# Sheet2.net
KiCad netlist of a schematic drawn in Altium Designer
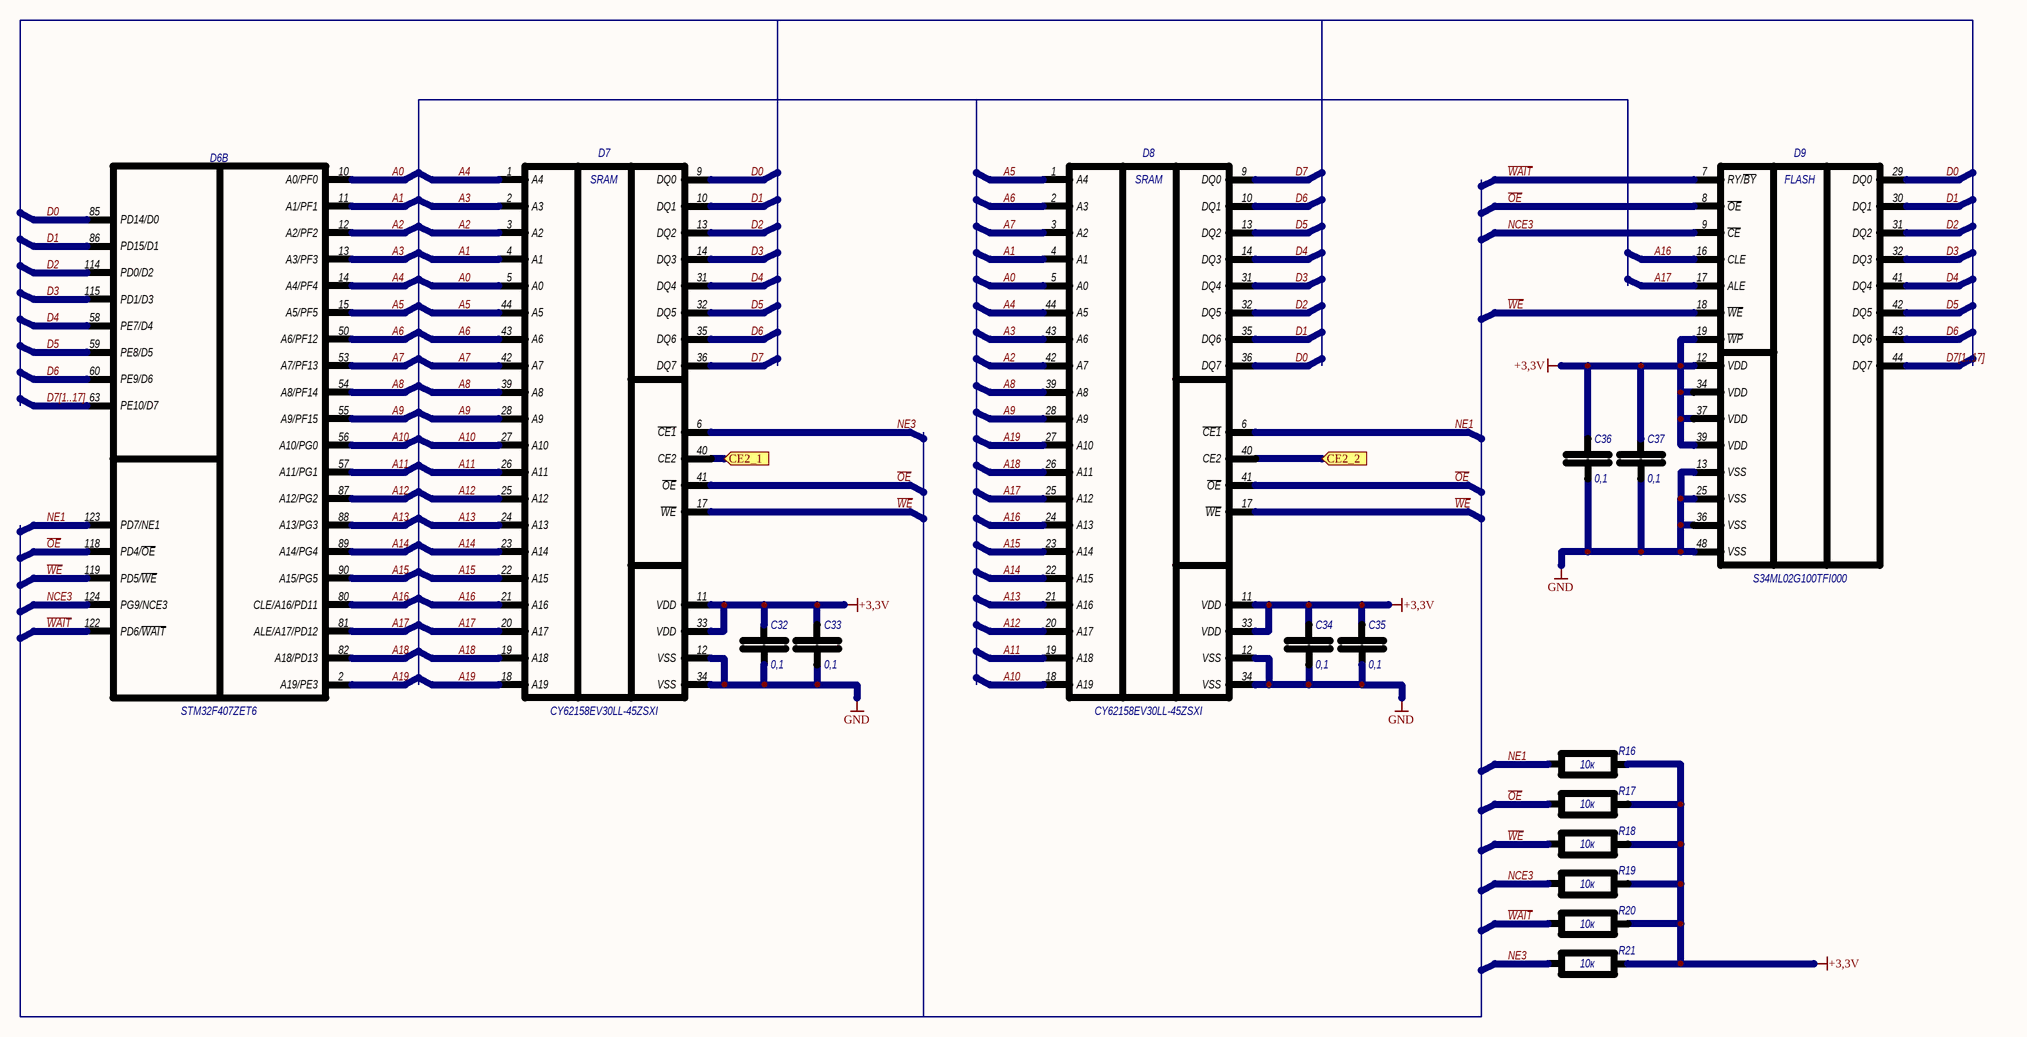
[diagram p0: Sheet2.SCHDOC]

(export (version "E")
  (design (tool "Eeschema 10.0.6"))
  (components
    (comp (ref "C32")
      (value "0,1")
      (footprint "0805")
      (description "КОНДЕНСАТОР")
      (fields (field (name "Comment") "К0805"))
      (libsource (lib "*") (part "К0805"))
    )
    (comp (ref "C33")
      (value "0,1")
      (footprint "0805")
      (description "КОНДЕНСАТОР")
      (fields (field (name "Comment") "К0805"))
      (libsource (lib "*") (part "К0805"))
    )
    (comp (ref "C34")
      (value "0,1")
      (footprint "0805")
      (description "КОНДЕНСАТОР")
      (fields (field (name "Comment") "К0805"))
      (libsource (lib "*") (part "К0805"))
    )
    (comp (ref "C35")
      (value "0,1")
      (footprint "0805")
      (description "КОНДЕНСАТОР")
      (fields (field (name "Comment") "К0805"))
      (libsource (lib "*") (part "К0805"))
    )
    (comp (ref "C36")
      (value "0,1")
      (footprint "0805")
      (description "КОНДЕНСАТОР")
      (fields (field (name "Comment") "К0805"))
      (libsource (lib "*") (part "К0805"))
    )
    (comp (ref "C37")
      (value "0,1")
      (footprint "0805")
      (description "КОНДЕНСАТОР")
      (fields (field (name "Comment") "К0805"))
      (libsource (lib "*") (part "К0805"))
    )
    (comp (ref "D6")
      (value "STM32F407ZET6")
      (footprint "LQFP-144")
      (libsource (lib "*") (part "STM32F407ZET6"))
    )
    (comp (ref "D7")
      (value "CY62158EV30LL-45ZSXI")
      (footprint "TSOP-44")
      (libsource (lib "*") (part "CY62158EV30LL-45ZSXI"))
    )
    (comp (ref "D8")
      (value "CY62158EV30LL-45ZSXI")
      (footprint "TSOP-44")
      (libsource (lib "*") (part "CY62158EV30LL-45ZSXI"))
    )
    (comp (ref "D9")
      (value "S34ML02G100TFI000")
      (footprint "TSSOP2-48")
      (libsource (lib "*") (part "S34ML02G100TFI000"))
    )
    (comp (ref "R16")
      (value "Р0805")
      (footprint "0805")
      (description "РЕЗИСТОР")
      (fields (field (name "ALTIUM_UNNAMED_1") "10к"))
      (libsource (lib "*") (part "Р0805"))
    )
    (comp (ref "R17")
      (value "Р0805")
      (footprint "0805")
      (description "РЕЗИСТОР")
      (fields (field (name "ALTIUM_UNNAMED_1") "10к"))
      (libsource (lib "*") (part "Р0805"))
    )
    (comp (ref "R18")
      (value "Р0805")
      (footprint "0805")
      (description "РЕЗИСТОР")
      (fields (field (name "ALTIUM_UNNAMED_1") "10к"))
      (libsource (lib "*") (part "Р0805"))
    )
    (comp (ref "R19")
      (value "Р0805")
      (footprint "0805")
      (description "РЕЗИСТОР")
      (fields (field (name "ALTIUM_UNNAMED_1") "10к"))
      (libsource (lib "*") (part "Р0805"))
    )
    (comp (ref "R20")
      (value "Р0805")
      (footprint "0805")
      (description "РЕЗИСТОР")
      (fields (field (name "ALTIUM_UNNAMED_1") "10к"))
      (libsource (lib "*") (part "Р0805"))
    )
    (comp (ref "R21")
      (value "Р0805")
      (footprint "0805")
      (description "РЕЗИСТОР")
      (fields (field (name "ALTIUM_UNNAMED_1") "10к"))
      (libsource (lib "*") (part "Р0805"))
    )
  )
  (nets
    (net (code "18") (name "+3,3V") (class "Default")
      (node (ref "C32") (pin "2") (pinfunction "2_2") (pintype "passive"))
      (node (ref "C33") (pin "2") (pinfunction "2_2") (pintype "passive"))
      (node (ref "C34") (pin "2") (pinfunction "2_2") (pintype "passive"))
      (node (ref "C35") (pin "2") (pinfunction "2_2") (pintype "passive"))
      (node (ref "C36") (pin "2") (pinfunction "2_2") (pintype "passive"))
      (node (ref "C37") (pin "2") (pinfunction "2_2") (pintype "passive"))
      (node (ref "D7") (pin "11") (pinfunction "VDD_11") (pintype "passive"))
      (node (ref "D7") (pin "33") (pinfunction "VDD_33") (pintype "passive"))
      (node (ref "D8") (pin "11") (pinfunction "VDD_11") (pintype "passive"))
      (node (ref "D8") (pin "33") (pinfunction "VDD_33") (pintype "passive"))
      (node (ref "D9") (pin "12") (pinfunction "VDD_12") (pintype "passive"))
      (node (ref "D9") (pin "19") (pinfunction "~{WP}_19") (pintype "passive"))
      (node (ref "D9") (pin "34") (pinfunction "VDD_34") (pintype "passive"))
      (node (ref "D9") (pin "37") (pinfunction "VDD_37") (pintype "passive"))
      (node (ref "D9") (pin "39") (pinfunction "VDD_39") (pintype "passive"))
      (node (ref "R16") (pin "1") (pinfunction "1_1") (pintype "passive"))
      (node (ref "R17") (pin "1") (pinfunction "1_1") (pintype "passive"))
      (node (ref "R18") (pin "1") (pinfunction "1_1") (pintype "passive"))
      (node (ref "R19") (pin "1") (pinfunction "1_1") (pintype "passive"))
      (node (ref "R20") (pin "1") (pinfunction "1_1") (pintype "passive"))
      (node (ref "R21") (pin "1") (pinfunction "1_1") (pintype "passive"))
    )
    (net (code "19") (name "/A0") (class "Default")
      (node (ref "D6") (pin "10") (pinfunction "A0/PF0_10") (pintype "passive"))
      (node (ref "D7") (pin "5") (pinfunction "A0_5") (pintype "passive"))
      (node (ref "D8") (pin "5") (pinfunction "A0_5") (pintype "passive"))
    )
    (net (code "20") (name "/A1") (class "Default")
      (node (ref "D6") (pin "11") (pinfunction "A1/PF1_11") (pintype "passive"))
      (node (ref "D7") (pin "4") (pinfunction "A1_4") (pintype "passive"))
      (node (ref "D8") (pin "4") (pinfunction "A1_4") (pintype "passive"))
    )
    (net (code "21") (name "/A2") (class "Default")
      (node (ref "D6") (pin "12") (pinfunction "A2/PF2_12") (pintype "passive"))
      (node (ref "D7") (pin "3") (pinfunction "A2_3") (pintype "passive"))
      (node (ref "D8") (pin "42") (pinfunction "A7_42") (pintype "passive"))
    )
    (net (code "22") (name "/A3") (class "Default")
      (node (ref "D6") (pin "13") (pinfunction "A3/PF3_13") (pintype "passive"))
      (node (ref "D7") (pin "2") (pinfunction "A3_2") (pintype "passive"))
      (node (ref "D8") (pin "43") (pinfunction "A6_43") (pintype "passive"))
    )
    (net (code "23") (name "/A4") (class "Default")
      (node (ref "D6") (pin "14") (pinfunction "A4/PF4_14") (pintype "passive"))
      (node (ref "D7") (pin "1") (pinfunction "A4_1") (pintype "passive"))
      (node (ref "D8") (pin "44") (pinfunction "A5_44") (pintype "passive"))
    )
    (net (code "24") (name "/A5") (class "Default")
      (node (ref "D6") (pin "15") (pinfunction "A5/PF5_15") (pintype "passive"))
      (node (ref "D7") (pin "44") (pinfunction "A5_44") (pintype "passive"))
      (node (ref "D8") (pin "1") (pinfunction "A4_1") (pintype "passive"))
    )
    (net (code "25") (name "/A6") (class "Default")
      (node (ref "D6") (pin "50") (pinfunction "A6/PF12_50") (pintype "passive"))
      (node (ref "D7") (pin "43") (pinfunction "A6_43") (pintype "passive"))
      (node (ref "D8") (pin "2") (pinfunction "A3_2") (pintype "passive"))
    )
    (net (code "26") (name "/A7") (class "Default")
      (node (ref "D6") (pin "53") (pinfunction "A7/PF13_53") (pintype "passive"))
      (node (ref "D7") (pin "42") (pinfunction "A7_42") (pintype "passive"))
      (node (ref "D8") (pin "3") (pinfunction "A2_3") (pintype "passive"))
    )
    (net (code "27") (name "/A8") (class "Default")
      (node (ref "D6") (pin "54") (pinfunction "A8/PF14_54") (pintype "passive"))
      (node (ref "D7") (pin "39") (pinfunction "A8_39") (pintype "passive"))
      (node (ref "D8") (pin "39") (pinfunction "A8_39") (pintype "passive"))
    )
    (net (code "28") (name "/A9") (class "Default")
      (node (ref "D6") (pin "55") (pinfunction "A9/PF15_55") (pintype "passive"))
      (node (ref "D7") (pin "28") (pinfunction "A9_28") (pintype "passive"))
      (node (ref "D8") (pin "28") (pinfunction "A9_28") (pintype "passive"))
    )
    (net (code "29") (name "/A10") (class "Default")
      (node (ref "D6") (pin "56") (pinfunction "A10/PG0_56") (pintype "passive"))
      (node (ref "D7") (pin "27") (pinfunction "A10_27") (pintype "passive"))
      (node (ref "D8") (pin "18") (pinfunction "A19_18") (pintype "passive"))
    )
    (net (code "30") (name "/A11") (class "Default")
      (node (ref "D6") (pin "57") (pinfunction "A11/PG1_57") (pintype "passive"))
      (node (ref "D7") (pin "26") (pinfunction "A11_26") (pintype "passive"))
      (node (ref "D8") (pin "19") (pinfunction "A18_19") (pintype "passive"))
    )
    (net (code "31") (name "/A12") (class "Default")
      (node (ref "D6") (pin "87") (pinfunction "A12/PG2_87") (pintype "passive"))
      (node (ref "D7") (pin "25") (pinfunction "A12_25") (pintype "passive"))
      (node (ref "D8") (pin "20") (pinfunction "A17_20") (pintype "passive"))
    )
    (net (code "32") (name "/A13") (class "Default")
      (node (ref "D6") (pin "88") (pinfunction "A13/PG3_88") (pintype "passive"))
      (node (ref "D7") (pin "24") (pinfunction "A13_24") (pintype "passive"))
      (node (ref "D8") (pin "21") (pinfunction "A16_21") (pintype "passive"))
    )
    (net (code "33") (name "/A14") (class "Default")
      (node (ref "D6") (pin "89") (pinfunction "A14/PG4_89") (pintype "passive"))
      (node (ref "D7") (pin "23") (pinfunction "A14_23") (pintype "passive"))
      (node (ref "D8") (pin "22") (pinfunction "A15_22") (pintype "passive"))
    )
    (net (code "34") (name "/A15") (class "Default")
      (node (ref "D6") (pin "90") (pinfunction "A15/PG5_90") (pintype "passive"))
      (node (ref "D7") (pin "22") (pinfunction "A15_22") (pintype "passive"))
      (node (ref "D8") (pin "23") (pinfunction "A14_23") (pintype "passive"))
    )
    (net (code "35") (name "/A16") (class "Default")
      (node (ref "D6") (pin "80") (pinfunction "CLE/A16/PD11_80") (pintype "passive"))
      (node (ref "D7") (pin "21") (pinfunction "A16_21") (pintype "passive"))
      (node (ref "D8") (pin "24") (pinfunction "A13_24") (pintype "passive"))
      (node (ref "D9") (pin "16") (pinfunction "CLE_16") (pintype "passive"))
    )
    (net (code "36") (name "/A17") (class "Default")
      (node (ref "D6") (pin "81") (pinfunction "ALE/A17/PD12_81") (pintype "passive"))
      (node (ref "D7") (pin "20") (pinfunction "A17_20") (pintype "passive"))
      (node (ref "D8") (pin "25") (pinfunction "A12_25") (pintype "passive"))
      (node (ref "D9") (pin "17") (pinfunction "ALE_17") (pintype "passive"))
    )
    (net (code "37") (name "/A18") (class "Default")
      (node (ref "D6") (pin "82") (pinfunction "A18/PD13_82") (pintype "passive"))
      (node (ref "D7") (pin "19") (pinfunction "A18_19") (pintype "passive"))
      (node (ref "D8") (pin "26") (pinfunction "A11_26") (pintype "passive"))
    )
    (net (code "38") (name "/A19") (class "Default")
      (node (ref "D6") (pin "2") (pinfunction "A19/PE3_2") (pintype "passive"))
      (node (ref "D7") (pin "18") (pinfunction "A19_18") (pintype "passive"))
      (node (ref "D8") (pin "27") (pinfunction "A10_27") (pintype "passive"))
    )
    (net (code "39") (name "/CE2_1") (class "Default")
      (node (ref "D7") (pin "40") (pinfunction "CE2_40") (pintype "passive"))
    )
    (net (code "40") (name "/CE2_2") (class "Default")
      (node (ref "D8") (pin "40") (pinfunction "CE2_40") (pintype "passive"))
    )
    (net (code "41") (name "/D0") (class "Default")
      (node (ref "D6") (pin "85") (pinfunction "PD14/D0_85") (pintype "passive"))
      (node (ref "D7") (pin "9") (pinfunction "DQ0_9") (pintype "passive"))
      (node (ref "D8") (pin "36") (pinfunction "DQ7_36") (pintype "passive"))
      (node (ref "D9") (pin "29") (pinfunction "DQ0_29") (pintype "passive"))
    )
    (net (code "42") (name "/D1") (class "Default")
      (node (ref "D6") (pin "86") (pinfunction "PD15/D1_86") (pintype "passive"))
      (node (ref "D7") (pin "10") (pinfunction "DQ1_10") (pintype "passive"))
      (node (ref "D8") (pin "35") (pinfunction "DQ6_35") (pintype "passive"))
      (node (ref "D9") (pin "30") (pinfunction "DQ1_30") (pintype "passive"))
    )
    (net (code "43") (name "/D2") (class "Default")
      (node (ref "D6") (pin "114") (pinfunction "PD0/D2_114") (pintype "passive"))
      (node (ref "D7") (pin "13") (pinfunction "DQ2_13") (pintype "passive"))
      (node (ref "D8") (pin "32") (pinfunction "DQ5_32") (pintype "passive"))
      (node (ref "D9") (pin "31") (pinfunction "DQ2_31") (pintype "passive"))
    )
    (net (code "44") (name "/D3") (class "Default")
      (node (ref "D6") (pin "115") (pinfunction "PD1/D3_115") (pintype "passive"))
      (node (ref "D7") (pin "14") (pinfunction "DQ3_14") (pintype "passive"))
      (node (ref "D8") (pin "31") (pinfunction "DQ4_31") (pintype "passive"))
      (node (ref "D9") (pin "32") (pinfunction "DQ3_32") (pintype "passive"))
    )
    (net (code "45") (name "/D4") (class "Default")
      (node (ref "D6") (pin "58") (pinfunction "PE7/D4_58") (pintype "passive"))
      (node (ref "D7") (pin "31") (pinfunction "DQ4_31") (pintype "passive"))
      (node (ref "D8") (pin "14") (pinfunction "DQ3_14") (pintype "passive"))
      (node (ref "D9") (pin "41") (pinfunction "DQ4_41") (pintype "passive"))
    )
    (net (code "46") (name "/D5") (class "Default")
      (node (ref "D6") (pin "59") (pinfunction "PE8/D5_59") (pintype "passive"))
      (node (ref "D7") (pin "32") (pinfunction "DQ5_32") (pintype "passive"))
      (node (ref "D8") (pin "13") (pinfunction "DQ2_13") (pintype "passive"))
      (node (ref "D9") (pin "42") (pinfunction "DQ5_42") (pintype "passive"))
    )
    (net (code "47") (name "/D6") (class "Default")
      (node (ref "D6") (pin "60") (pinfunction "PE9/D6_60") (pintype "passive"))
      (node (ref "D7") (pin "35") (pinfunction "DQ6_35") (pintype "passive"))
      (node (ref "D8") (pin "10") (pinfunction "DQ1_10") (pintype "passive"))
      (node (ref "D9") (pin "43") (pinfunction "DQ6_43") (pintype "passive"))
    )
    (net (code "48") (name "/D7") (class "Default")
      (node (ref "D7") (pin "36") (pinfunction "DQ7_36") (pintype "passive"))
      (node (ref "D8") (pin "9") (pinfunction "DQ0_9") (pintype "passive"))
    )
    (net (code "49") (name "/D7[1..17]") (class "Default")
      (node (ref "D6") (pin "63") (pinfunction "PE10/D7_63") (pintype "passive"))
      (node (ref "D9") (pin "44") (pinfunction "DQ7_44") (pintype "passive"))
    )
    (net (code "50") (name "/NCE3") (class "Default")
      (node (ref "D6") (pin "124") (pinfunction "PG9/NCE3_124") (pintype "passive"))
      (node (ref "D9") (pin "9") (pinfunction "~{CE}_9") (pintype "passive"))
      (node (ref "R19") (pin "2") (pinfunction "2_2") (pintype "passive"))
    )
    (net (code "51") (name "/NE1") (class "Default")
      (node (ref "D6") (pin "123") (pinfunction "PD7/NE1_123") (pintype "passive"))
      (node (ref "D8") (pin "6") (pinfunction "~{CE1}_6") (pintype "passive"))
      (node (ref "R16") (pin "2") (pinfunction "2_2") (pintype "passive"))
    )
    (net (code "52") (name "/NE3") (class "Default")
      (node (ref "D7") (pin "6") (pinfunction "~{CE1}_6") (pintype "passive"))
      (node (ref "R21") (pin "2") (pinfunction "2_2") (pintype "passive"))
    )
    (net (code "53") (name "/~{OE}") (class "Default")
      (node (ref "D6") (pin "118") (pinfunction "PD4/~{OE}_118") (pintype "passive"))
      (node (ref "D7") (pin "41") (pinfunction "~{OE}_41") (pintype "passive"))
      (node (ref "D8") (pin "41") (pinfunction "~{OE}_41") (pintype "passive"))
      (node (ref "D9") (pin "8") (pinfunction "~{OE}_8") (pintype "passive"))
      (node (ref "R17") (pin "2") (pinfunction "2_2") (pintype "passive"))
    )
    (net (code "54") (name "/~{WAIT}") (class "Default")
      (node (ref "D6") (pin "122") (pinfunction "PD6/~{WAIT}_122") (pintype "passive"))
      (node (ref "D9") (pin "7") (pinfunction "RY/~{BY}_7") (pintype "passive"))
      (node (ref "R20") (pin "2") (pinfunction "2_2") (pintype "passive"))
    )
    (net (code "55") (name "/~{WE}") (class "Default")
      (node (ref "D6") (pin "119") (pinfunction "PD5/~{WE}_119") (pintype "passive"))
      (node (ref "D7") (pin "17") (pinfunction "~{WE}_17") (pintype "passive"))
      (node (ref "D8") (pin "17") (pinfunction "~{WE}_17") (pintype "passive"))
      (node (ref "D9") (pin "18") (pinfunction "~{WE}_18") (pintype "passive"))
      (node (ref "R18") (pin "2") (pinfunction "2_2") (pintype "passive"))
    )
    (net (code "56") (name "GND") (class "Default")
      (node (ref "C32") (pin "1") (pinfunction "1_1") (pintype "passive"))
      (node (ref "C33") (pin "1") (pinfunction "1_1") (pintype "passive"))
      (node (ref "C34") (pin "1") (pinfunction "1_1") (pintype "passive"))
      (node (ref "C35") (pin "1") (pinfunction "1_1") (pintype "passive"))
      (node (ref "C36") (pin "1") (pinfunction "1_1") (pintype "passive"))
      (node (ref "C37") (pin "1") (pinfunction "1_1") (pintype "passive"))
      (node (ref "D7") (pin "12") (pinfunction "VSS_12") (pintype "passive"))
      (node (ref "D7") (pin "34") (pinfunction "VSS_34") (pintype "passive"))
      (node (ref "D8") (pin "12") (pinfunction "VSS_12") (pintype "passive"))
      (node (ref "D8") (pin "34") (pinfunction "VSS_34") (pintype "passive"))
      (node (ref "D9") (pin "13") (pinfunction "VSS_13") (pintype "passive"))
      (node (ref "D9") (pin "25") (pinfunction "VSS_25") (pintype "passive"))
      (node (ref "D9") (pin "36") (pinfunction "VSS_36") (pintype "passive"))
      (node (ref "D9") (pin "48") (pinfunction "VSS_48") (pintype "passive"))
    )
    (net (code "57") (name "unconnected-(D6-Pad49)") (class "Default")
      (node (ref "D6") (pin "49") (pintype "passive"))
    )
    (net (code "58") (name "unconnected-(D7-Pad7)") (class "Default")
      (node (ref "D7") (pin "7") (pintype "passive"))
    )
    (net (code "59") (name "unconnected-(D7-Pad8)") (class "Default")
      (node (ref "D7") (pin "8") (pintype "passive"))
    )
    (net (code "60") (name "unconnected-(D7-Pad15)") (class "Default")
      (node (ref "D7") (pin "15") (pintype "passive"))
    )
    (net (code "61") (name "unconnected-(D7-Pad16)") (class "Default")
      (node (ref "D7") (pin "16") (pintype "passive"))
    )
    (net (code "62") (name "unconnected-(D7-Pad29)") (class "Default")
      (node (ref "D7") (pin "29") (pintype "passive"))
    )
    (net (code "63") (name "unconnected-(D7-Pad30)") (class "Default")
      (node (ref "D7") (pin "30") (pintype "passive"))
    )
    (net (code "64") (name "unconnected-(D7-Pad37)") (class "Default")
      (node (ref "D7") (pin "37") (pintype "passive"))
    )
    (net (code "65") (name "unconnected-(D7-Pad38)") (class "Default")
      (node (ref "D7") (pin "38") (pintype "passive"))
    )
    (net (code "66") (name "unconnected-(D8-Pad7)") (class "Default")
      (node (ref "D8") (pin "7") (pintype "passive"))
    )
    (net (code "67") (name "unconnected-(D8-Pad8)") (class "Default")
      (node (ref "D8") (pin "8") (pintype "passive"))
    )
    (net (code "68") (name "unconnected-(D8-Pad15)") (class "Default")
      (node (ref "D8") (pin "15") (pintype "passive"))
    )
    (net (code "69") (name "unconnected-(D8-Pad16)") (class "Default")
      (node (ref "D8") (pin "16") (pintype "passive"))
    )
    (net (code "70") (name "unconnected-(D8-Pad29)") (class "Default")
      (node (ref "D8") (pin "29") (pintype "passive"))
    )
    (net (code "71") (name "unconnected-(D8-Pad30)") (class "Default")
      (node (ref "D8") (pin "30") (pintype "passive"))
    )
    (net (code "72") (name "unconnected-(D8-Pad37)") (class "Default")
      (node (ref "D8") (pin "37") (pintype "passive"))
    )
    (net (code "73") (name "unconnected-(D8-Pad38)") (class "Default")
      (node (ref "D8") (pin "38") (pintype "passive"))
    )
    (net (code "74") (name "unconnected-(D9-Pad1)") (class "Default")
      (node (ref "D9") (pin "1") (pintype "passive"))
    )
    (net (code "75") (name "unconnected-(D9-Pad2)") (class "Default")
      (node (ref "D9") (pin "2") (pintype "passive"))
    )
    (net (code "76") (name "unconnected-(D9-Pad3)") (class "Default")
      (node (ref "D9") (pin "3") (pintype "passive"))
    )
    (net (code "77") (name "unconnected-(D9-Pad4)") (class "Default")
      (node (ref "D9") (pin "4") (pintype "passive"))
    )
    (net (code "78") (name "unconnected-(D9-Pad5)") (class "Default")
      (node (ref "D9") (pin "5") (pintype "passive"))
    )
    (net (code "79") (name "unconnected-(D9-Pad6)") (class "Default")
      (node (ref "D9") (pin "6") (pintype "passive"))
    )
    (net (code "80") (name "unconnected-(D9-Pad10)") (class "Default")
      (node (ref "D9") (pin "10") (pintype "passive"))
    )
    (net (code "81") (name "unconnected-(D9-Pad11)") (class "Default")
      (node (ref "D9") (pin "11") (pintype "passive"))
    )
    (net (code "82") (name "unconnected-(D9-Pad14)") (class "Default")
      (node (ref "D9") (pin "14") (pintype "passive"))
    )
    (net (code "83") (name "unconnected-(D9-Pad15)") (class "Default")
      (node (ref "D9") (pin "15") (pintype "passive"))
    )
    (net (code "84") (name "unconnected-(D9-Pad20)") (class "Default")
      (node (ref "D9") (pin "20") (pintype "passive"))
    )
    (net (code "85") (name "unconnected-(D9-Pad21)") (class "Default")
      (node (ref "D9") (pin "21") (pintype "passive"))
    )
    (net (code "86") (name "unconnected-(D9-Pad22)") (class "Default")
      (node (ref "D9") (pin "22") (pintype "passive"))
    )
    (net (code "87") (name "unconnected-(D9-Pad23)") (class "Default")
      (node (ref "D9") (pin "23") (pintype "passive"))
    )
    (net (code "88") (name "unconnected-(D9-Pad24)") (class "Default")
      (node (ref "D9") (pin "24") (pintype "passive"))
    )
    (net (code "89") (name "unconnected-(D9-Pad26)") (class "Default")
      (node (ref "D9") (pin "26") (pintype "passive"))
    )
    (net (code "90") (name "unconnected-(D9-Pad27)") (class "Default")
      (node (ref "D9") (pin "27") (pintype "passive"))
    )
    (net (code "91") (name "unconnected-(D9-Pad28)") (class "Default")
      (node (ref "D9") (pin "28") (pintype "passive"))
    )
    (net (code "92") (name "unconnected-(D9-Pad33)") (class "Default")
      (node (ref "D9") (pin "33") (pintype "passive"))
    )
    (net (code "93") (name "unconnected-(D9-Pad35)") (class "Default")
      (node (ref "D9") (pin "35") (pintype "passive"))
    )
    (net (code "94") (name "unconnected-(D9-Pad38)") (class "Default")
      (node (ref "D9") (pin "38") (pintype "passive"))
    )
    (net (code "95") (name "unconnected-(D9-Pad40)") (class "Default")
      (node (ref "D9") (pin "40") (pintype "passive"))
    )
    (net (code "96") (name "unconnected-(D9-Pad45)") (class "Default")
      (node (ref "D9") (pin "45") (pintype "passive"))
    )
    (net (code "97") (name "unconnected-(D9-Pad46)") (class "Default")
      (node (ref "D9") (pin "46") (pintype "passive"))
    )
    (net (code "98") (name "unconnected-(D9-Pad47)") (class "Default")
      (node (ref "D9") (pin "47") (pintype "passive"))
    )
  )
)
